# xdip_matching_balun.net
KiCad netlist of a schematic drawn in Altium Designer
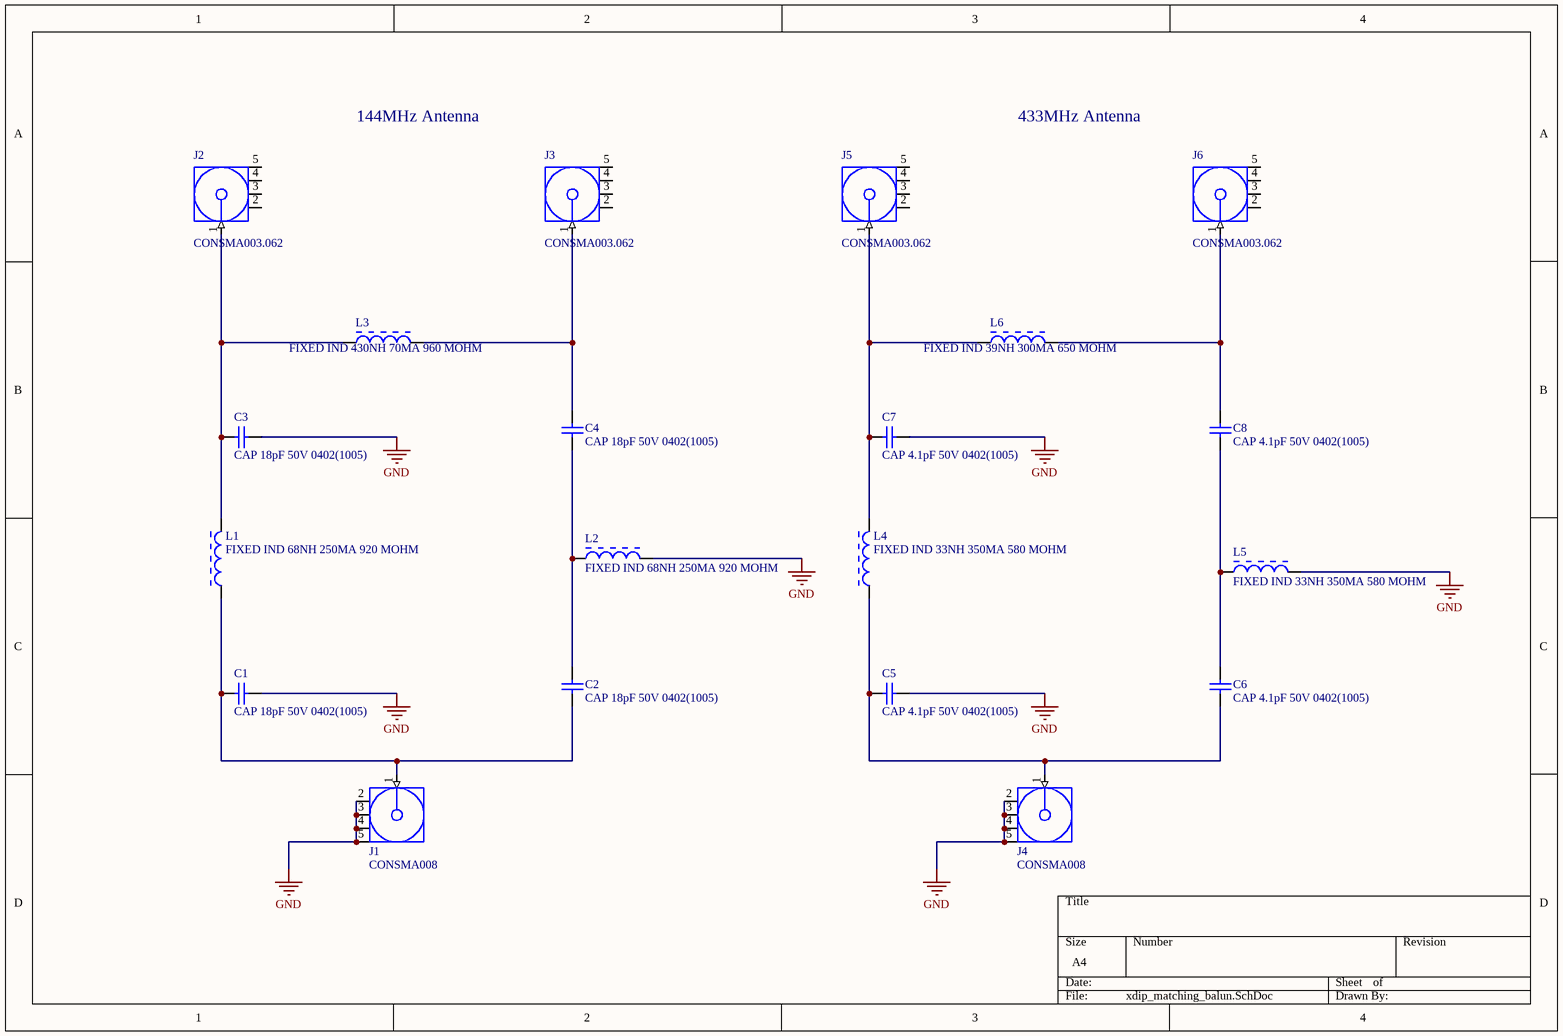
[diagram p0: xdip_matching_balun.SchDoc]

(export (version "E")
  (design (tool "Eeschema 10.0.6"))
  (components
    (comp (ref "C1")
      (value "CAP 18pF 50V 0402(1005)")
      (footprint "CAPC0402(1005)60_M")
      (description "CAP 18pF 50V ±1% 0402 (1005 Metric) Thickness 0.6mm SMD")
      (fields (field (name "TOLERANCE") "Â±1%"))
      (libsource (lib "Altium Content Vault") (part "CMP-1034-00862-1"))
    )
    (comp (ref "C2")
      (value "CAP 18pF 50V 0402(1005)")
      (footprint "CAPC0402(1005)60_M")
      (description "CAP 18pF 50V ±1% 0402 (1005 Metric) Thickness 0.6mm SMD")
      (fields (field (name "TOLERANCE") "Â±1%"))
      (libsource (lib "Altium Content Vault") (part "CMP-1034-00862-1"))
    )
    (comp (ref "C3")
      (value "CAP 18pF 50V 0402(1005)")
      (footprint "CAPC0402(1005)60_M")
      (description "CAP 18pF 50V ±1% 0402 (1005 Metric) Thickness 0.6mm SMD")
      (fields (field (name "TOLERANCE") "Â±1%"))
      (libsource (lib "Altium Content Vault") (part "CMP-1034-00862-1"))
    )
    (comp (ref "C4")
      (value "CAP 18pF 50V 0402(1005)")
      (footprint "CAPC0402(1005)60_M")
      (description "CAP 18pF 50V ±1% 0402 (1005 Metric) Thickness 0.6mm SMD")
      (fields (field (name "TOLERANCE") "Â±1%"))
      (libsource (lib "Altium Content Vault") (part "CMP-1034-00862-1"))
    )
    (comp (ref "C5")
      (value "CAP 4.1pF 50V 0402(1005)")
      (footprint "CAPC0402(1005)60_M")
      (description "CAP 4.1pF 50V ±0.1pF 0402 (1005 Metric) Thickness 0.6mm SMD")
      (fields (field (name "TOLERANCE") "Â±0.1pF"))
      (libsource (lib "Altium Content Vault") (part "CMP-1034-00324-1"))
    )
    (comp (ref "C6")
      (value "CAP 4.1pF 50V 0402(1005)")
      (footprint "CAPC0402(1005)60_M")
      (description "CAP 4.1pF 50V ±0.1pF 0402 (1005 Metric) Thickness 0.6mm SMD")
      (fields (field (name "TOLERANCE") "Â±0.1pF"))
      (libsource (lib "Altium Content Vault") (part "CMP-1034-00324-1"))
    )
    (comp (ref "C7")
      (value "CAP 4.1pF 50V 0402(1005)")
      (footprint "CAPC0402(1005)60_M")
      (description "CAP 4.1pF 50V ±0.1pF 0402 (1005 Metric) Thickness 0.6mm SMD")
      (fields (field (name "TOLERANCE") "Â±0.1pF"))
      (libsource (lib "Altium Content Vault") (part "CMP-1034-00324-1"))
    )
    (comp (ref "C8")
      (value "CAP 4.1pF 50V 0402(1005)")
      (footprint "CAPC0402(1005)60_M")
      (description "CAP 4.1pF 50V ±0.1pF 0402 (1005 Metric) Thickness 0.6mm SMD")
      (fields (field (name "TOLERANCE") "Â±0.1pF"))
      (libsource (lib "Altium Content Vault") (part "CAP"))
    )
    (comp (ref "J1")
      (value "CONSMA008")
      (footprint "CON-SMA-L")
      (description "SMA Female PCB Mount Connector - Extended")
      (libsource (lib "Altium Content Vault") (part "CMP-0168-00003-1"))
    )
    (comp (ref "J2")
      (value "CONSMA003.062")
      (footprint "CON-SMA-EDGE062")
      (description "SMA Female Edge Mount Connector for 0.062\" Thick Board")
      (libsource (lib "Altium Content Vault") (part "CN-1P-F-RF5"))
    )
    (comp (ref "J3")
      (value "CONSMA003.062")
      (footprint "CON-SMA-EDGE062")
      (description "SMA Female Edge Mount Connector for 0.062\" Thick Board")
      (libsource (lib "Altium Content Vault") (part "CN-1P-F-RF5"))
    )
    (comp (ref "J4")
      (value "CONSMA008")
      (footprint "CON-SMA-L")
      (description "SMA Female PCB Mount Connector - Extended")
      (libsource (lib "Altium Content Vault") (part "CMP-0168-00003-1"))
    )
    (comp (ref "J5")
      (value "CONSMA003.062")
      (footprint "CON-SMA-EDGE062")
      (description "SMA Female Edge Mount Connector for 0.062\" Thick Board")
      (libsource (lib "Altium Content Vault") (part "CN-1P-F-RF5"))
    )
    (comp (ref "J6")
      (value "CONSMA003.062")
      (footprint "CON-SMA-EDGE062")
      (description "SMA Female Edge Mount Connector for 0.062\" Thick Board")
      (libsource (lib "Altium Content Vault") (part "CN-1P-F-RF5"))
    )
    (comp (ref "L1")
      (value "FIXED IND 68NH 250MA 920 MOHM")
      (footprint "MURA-IND0402_V")
      (fields (field (name "MANUFACTURER") "Murata") (field (name "PARTNUMBER") "LQG15HS2N0S02D"))
      (libsource (lib "Altium Content Vault") (part "MURA-INDC-2"))
    )
    (comp (ref "L2")
      (value "FIXED IND 68NH 250MA 920 MOHM")
      (footprint "MURA-IND0402_V")
      (fields (field (name "MANUFACTURER") "Murata") (field (name "PARTNUMBER") "LQG15HS2N0S02D"))
      (libsource (lib "Altium Content Vault") (part "CMP-0499-00001-3"))
    )
    (comp (ref "L3")
      (value "FIXED IND 430NH 70MA 960 MOHM")
      (footprint "MURA-IND0402_V")
      (fields (field (name "MANUFACTURER") "Murata") (field (name "PARTNUMBER") "LQG15HS2N0S02D"))
      (libsource (lib "Altium Content Vault") (part "CMP-0499-00001-3"))
    )
    (comp (ref "L4")
      (value "FIXED IND 33NH 350MA 580 MOHM")
      (footprint "MURA-IND0402_V")
      (fields (field (name "MANUFACTURER") "Murata") (field (name "PARTNUMBER") "LQG15HS2N0S02D"))
      (libsource (lib "Altium Content Vault") (part "CMP-0499-00001-3"))
    )
    (comp (ref "L5")
      (value "FIXED IND 33NH 350MA 580 MOHM")
      (footprint "MURA-IND0402_V")
      (fields (field (name "MANUFACTURER") "Murata") (field (name "PARTNUMBER") "LQG15HS2N0S02D"))
      (libsource (lib "Altium Content Vault") (part "CMP-0499-00001-3"))
    )
    (comp (ref "L6")
      (value "FIXED IND 39NH 300MA 650 MOHM")
      (footprint "MURA-IND0402_V")
      (fields (field (name "MANUFACTURER") "Murata") (field (name "PARTNUMBER") "LQG15HS2N0S02D"))
      (libsource (lib "Altium Content Vault") (part "CMP-0499-00001-3"))
    )
  )
  (nets
    (net (code "1") (name "GND") (class "Default")
      (node (ref "C1") (pin "2") (pinfunction "2_2") (pintype "passive"))
      (node (ref "C3") (pin "2") (pinfunction "2_2") (pintype "passive"))
      (node (ref "C5") (pin "2") (pinfunction "2_2") (pintype "passive"))
      (node (ref "C7") (pin "2") (pinfunction "2_2") (pintype "passive"))
      (node (ref "J1") (pin "2") (pinfunction "GND_2") (pintype "power_in"))
      (node (ref "J1") (pin "3") (pinfunction "GND_3") (pintype "power_in"))
      (node (ref "J1") (pin "4") (pinfunction "GND_4") (pintype "power_in"))
      (node (ref "J1") (pin "5") (pinfunction "GND_5") (pintype "power_in"))
      (node (ref "J4") (pin "2") (pinfunction "GND_2") (pintype "power_in"))
      (node (ref "J4") (pin "3") (pinfunction "GND_3") (pintype "power_in"))
      (node (ref "J4") (pin "4") (pinfunction "GND_4") (pintype "power_in"))
      (node (ref "J4") (pin "5") (pinfunction "GND_5") (pintype "power_in"))
      (node (ref "L2") (pin "2") (pinfunction "2_2") (pintype "passive"))
      (node (ref "L5") (pin "2") (pinfunction "2_2") (pintype "passive"))
    )
    (net (code "2") (name "Net-(C2-Pad2)") (class "Default")
      (node (ref "C2") (pin "2") (pinfunction "2_2") (pintype "passive"))
      (node (ref "C4") (pin "1") (pinfunction "1_1") (pintype "passive"))
      (node (ref "L2") (pin "1") (pinfunction "1_1") (pintype "passive"))
    )
    (net (code "3") (name "Net-(C6-Pad2)") (class "Default")
      (node (ref "C6") (pin "2") (pinfunction "2_2") (pintype "passive"))
      (node (ref "C8") (pin "1") (pinfunction "1_1") (pintype "passive"))
      (node (ref "L5") (pin "1") (pinfunction "1_1") (pintype "passive"))
    )
    (net (code "4") (name "Net-(J1-Signal)") (class "Default")
      (node (ref "C1") (pin "1") (pinfunction "1_1") (pintype "passive"))
      (node (ref "C2") (pin "1") (pinfunction "1_1") (pintype "passive"))
      (node (ref "J1") (pin "1") (pinfunction "Signal_1") (pintype "input"))
      (node (ref "L1") (pin "1") (pinfunction "1_1") (pintype "passive"))
    )
    (net (code "5") (name "Net-(J2-Signal)") (class "Default")
      (node (ref "C3") (pin "1") (pinfunction "1_1") (pintype "passive"))
      (node (ref "J2") (pin "1") (pinfunction "Signal_1") (pintype "input"))
      (node (ref "L1") (pin "2") (pinfunction "2_2") (pintype "passive"))
      (node (ref "L3") (pin "1") (pinfunction "1_1") (pintype "passive"))
    )
    (net (code "6") (name "Net-(J3-Signal)") (class "Default")
      (node (ref "C4") (pin "2") (pinfunction "2_2") (pintype "passive"))
      (node (ref "J3") (pin "1") (pinfunction "Signal_1") (pintype "input"))
      (node (ref "L3") (pin "2") (pinfunction "2_2") (pintype "passive"))
    )
    (net (code "7") (name "Net-(J4-Signal)") (class "Default")
      (node (ref "C5") (pin "1") (pinfunction "1_1") (pintype "passive"))
      (node (ref "C6") (pin "1") (pinfunction "1_1") (pintype "passive"))
      (node (ref "J4") (pin "1") (pinfunction "Signal_1") (pintype "input"))
      (node (ref "L4") (pin "1") (pinfunction "1_1") (pintype "passive"))
    )
    (net (code "8") (name "Net-(J5-Signal)") (class "Default")
      (node (ref "C7") (pin "1") (pinfunction "1_1") (pintype "passive"))
      (node (ref "J5") (pin "1") (pinfunction "Signal_1") (pintype "input"))
      (node (ref "L4") (pin "2") (pinfunction "2_2") (pintype "passive"))
      (node (ref "L6") (pin "1") (pinfunction "1_1") (pintype "passive"))
    )
    (net (code "9") (name "Net-(J6-Signal)") (class "Default")
      (node (ref "C8") (pin "2") (pinfunction "2_2") (pintype "passive"))
      (node (ref "J6") (pin "1") (pinfunction "Signal_1") (pintype "input"))
      (node (ref "L6") (pin "2") (pinfunction "2_2") (pintype "passive"))
    )
    (net (code "10") (name "unconnected-(J2-GND-Pad2)") (class "Default")
      (node (ref "J2") (pin "2") (pinfunction "GND_2") (pintype "power_in"))
    )
    (net (code "11") (name "unconnected-(J2-GND-Pad3)") (class "Default")
      (node (ref "J2") (pin "3") (pinfunction "GND_3") (pintype "power_in"))
    )
    (net (code "12") (name "unconnected-(J2-GND-Pad4)") (class "Default")
      (node (ref "J2") (pin "4") (pinfunction "GND_4") (pintype "power_in"))
    )
    (net (code "13") (name "unconnected-(J2-GND-Pad5)") (class "Default")
      (node (ref "J2") (pin "5") (pinfunction "GND_5") (pintype "power_in"))
    )
    (net (code "14") (name "unconnected-(J3-GND-Pad2)") (class "Default")
      (node (ref "J3") (pin "2") (pinfunction "GND_2") (pintype "power_in"))
    )
    (net (code "15") (name "unconnected-(J3-GND-Pad3)") (class "Default")
      (node (ref "J3") (pin "3") (pinfunction "GND_3") (pintype "power_in"))
    )
    (net (code "16") (name "unconnected-(J3-GND-Pad4)") (class "Default")
      (node (ref "J3") (pin "4") (pinfunction "GND_4") (pintype "power_in"))
    )
    (net (code "17") (name "unconnected-(J3-GND-Pad5)") (class "Default")
      (node (ref "J3") (pin "5") (pinfunction "GND_5") (pintype "power_in"))
    )
    (net (code "18") (name "unconnected-(J5-GND-Pad2)") (class "Default")
      (node (ref "J5") (pin "2") (pinfunction "GND_2") (pintype "power_in"))
    )
    (net (code "19") (name "unconnected-(J5-GND-Pad3)") (class "Default")
      (node (ref "J5") (pin "3") (pinfunction "GND_3") (pintype "power_in"))
    )
    (net (code "20") (name "unconnected-(J5-GND-Pad4)") (class "Default")
      (node (ref "J5") (pin "4") (pinfunction "GND_4") (pintype "power_in"))
    )
    (net (code "21") (name "unconnected-(J5-GND-Pad5)") (class "Default")
      (node (ref "J5") (pin "5") (pinfunction "GND_5") (pintype "power_in"))
    )
    (net (code "22") (name "unconnected-(J6-GND-Pad2)") (class "Default")
      (node (ref "J6") (pin "2") (pinfunction "GND_2") (pintype "power_in"))
    )
    (net (code "23") (name "unconnected-(J6-GND-Pad3)") (class "Default")
      (node (ref "J6") (pin "3") (pinfunction "GND_3") (pintype "power_in"))
    )
    (net (code "24") (name "unconnected-(J6-GND-Pad4)") (class "Default")
      (node (ref "J6") (pin "4") (pinfunction "GND_4") (pintype "power_in"))
    )
    (net (code "25") (name "unconnected-(J6-GND-Pad5)") (class "Default")
      (node (ref "J6") (pin "5") (pinfunction "GND_5") (pintype "power_in"))
    )
  )
)
